# RMII.net
KiCad netlist of a schematic drawn in Altium Designer
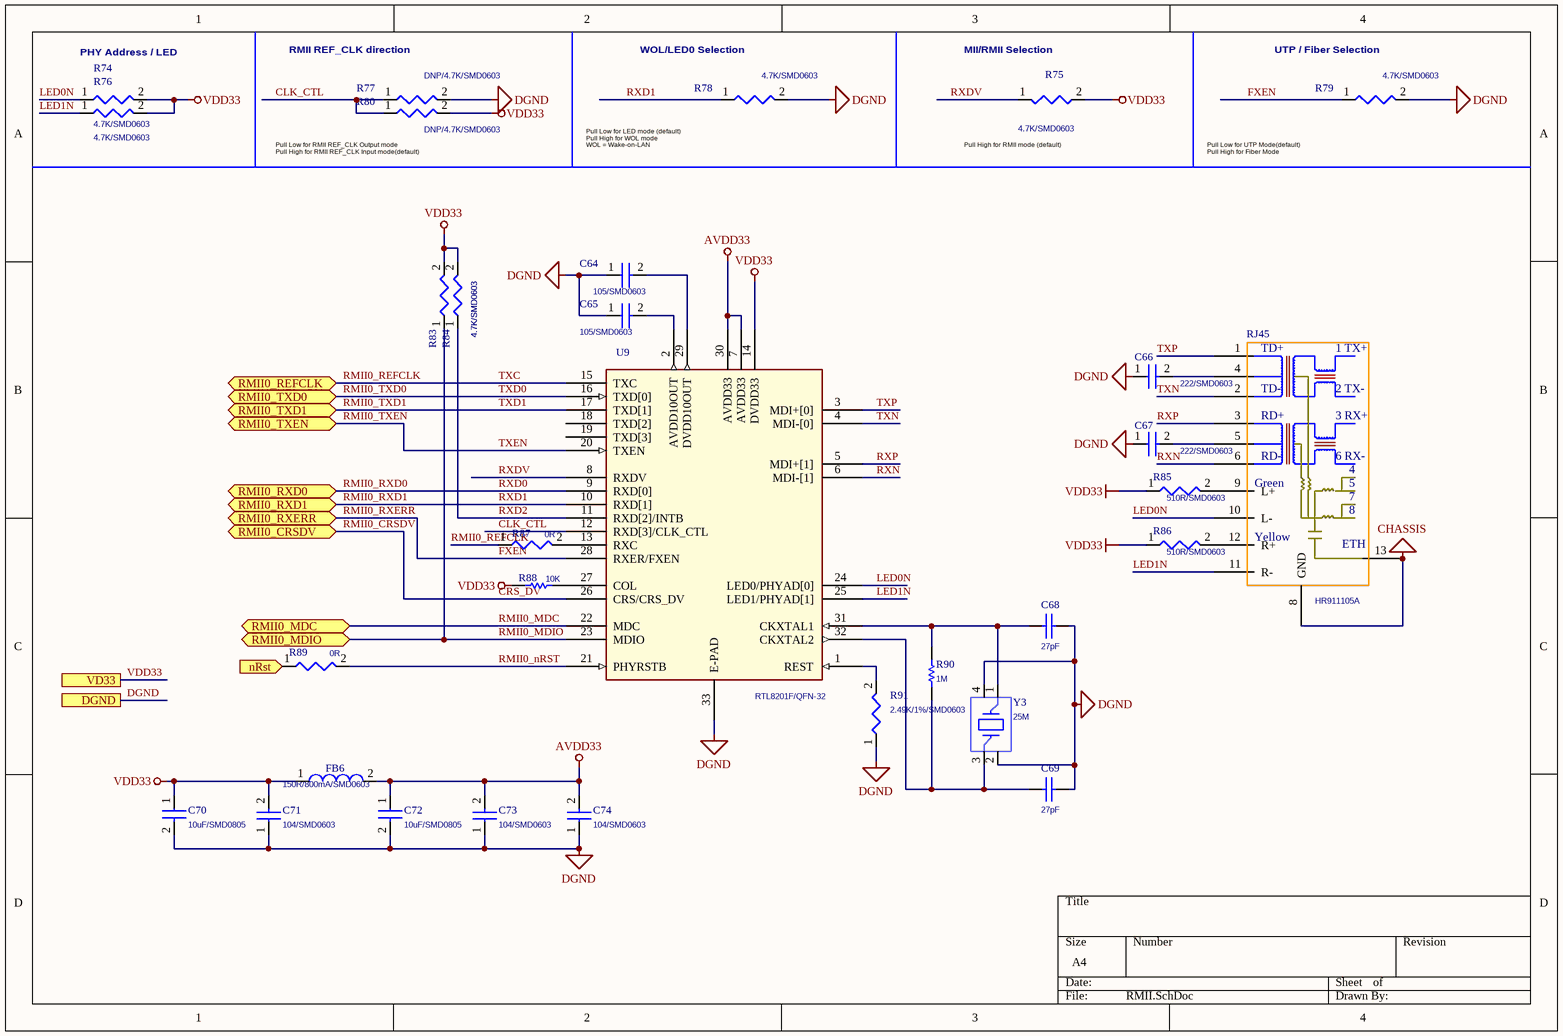
[diagram p0: RMII.SchDoc]

(export (version "E")
  (design (tool "Eeschema 10.0.6"))
  (components
    (comp (ref "C64") (value "105/SMD0603") (footprint "0603C") (libsource (lib "*") (part "C/SMD0603")))
    (comp (ref "C65") (value "105/SMD0603") (footprint "0603C") (libsource (lib "*") (part "C/SMD0603")))
    (comp (ref "C66") (value "222/SMD0603") (footprint "0603C") (libsource (lib "*") (part "C/SMD0603")))
    (comp (ref "C67") (value "222/SMD0603") (footprint "0603C") (libsource (lib "*") (part "C/SMD0603")))
    (comp (ref "C68")
      (value "27pF")
      (footprint "0603C")
      (description "Capacitor")
      (libsource (lib "STM32F103ZET6") (part "CAP"))
    )
    (comp (ref "C69")
      (value "27pF")
      (footprint "0603C")
      (description "Capacitor")
      (libsource (lib "STM32F103ZET6") (part "CAP"))
    )
    (comp (ref "C70") (value "10uF/SMD0805") (footprint "C0805") (libsource (lib "*") (part "C/SMD0805")))
    (comp (ref "C71") (value "104/SMD0603") (footprint "0603C") (libsource (lib "*") (part "C/SMD0603")))
    (comp (ref "C72") (value "10uF/SMD0805") (footprint "C0805") (libsource (lib "*") (part "C/SMD0805")))
    (comp (ref "C73") (value "104/SMD0603") (footprint "0603C") (libsource (lib "*") (part "C/SMD0603")))
    (comp (ref "C74") (value "104/SMD0603") (footprint "0603C") (libsource (lib "*") (part "C/SMD0603")))
    (comp (ref "FB6")
      (value "150R/800mA/SMD0603")
      (footprint "0603R")
      (libsource (lib "*") (part "FB/SMD0603"))
    )
    (comp (ref "R74") (value "4.7K/SMD0603") (footprint "0603R") (libsource (lib "*") (part "R/SMD0603")))
    (comp (ref "R75") (value "4.7K/SMD0603") (footprint "0603R") (libsource (lib "*") (part "R/SMD0603")))
    (comp (ref "R76") (value "4.7K/SMD0603") (footprint "0603R") (libsource (lib "*") (part "R/SMD0603")))
    (comp (ref "R77") (value "DNP/4.7K/SMD0603") (footprint "0603R") (libsource (lib "*") (part "R/SMD0603")))
    (comp (ref "R78") (value "4.7K/SMD0603") (footprint "0603R") (libsource (lib "*") (part "R/SMD0603")))
    (comp (ref "R79") (value "4.7K/SMD0603") (footprint "0603R") (libsource (lib "*") (part "R/SMD0603")))
    (comp (ref "R80") (value "DNP/4.7K/SMD0603") (footprint "0603R") (libsource (lib "*") (part "R/SMD0603")))
    (comp (ref "R83") (value "4.7K/SMD0603") (footprint "0603R") (libsource (lib "*") (part "R/SMD0603")))
    (comp (ref "R84") (value "4.7K/SMD0603") (footprint "0603R") (libsource (lib "*") (part "R/SMD0603")))
    (comp (ref "R85") (value "510R/SMD0603") (footprint "0603R") (libsource (lib "*") (part "R/SMD0603")))
    (comp (ref "R86") (value "510R/SMD0603") (footprint "0603R") (libsource (lib "*") (part "R/SMD0603")))
    (comp (ref "R87") (value "0R") (footprint "0603R") (libsource (lib "*") (part "R/SMD0603")))
    (comp (ref "R88")
      (value "10K")
      (footprint "0603C")
      (description "Resistor")
      (fields (field (name "PUBLISHER") "Altium Limited"))
      (libsource (lib "STM32F103ZET6") (part "Res1"))
    )
    (comp (ref "R89") (value "0R") (footprint "0603R") (libsource (lib "*") (part "R/SMD0603")))
    (comp (ref "R90")
      (value "1M")
      (footprint "0603C")
      (description "Resistor")
      (fields (field (name "PUBLISHER") "Altium Limited"))
      (libsource (lib "STM32F103ZET6") (part "Res1"))
    )
    (comp (ref "R91") (value "2.49K/1%/SMD0603") (footprint "0603R") (libsource (lib "*") (part "R/SMD0603")))
    (comp (ref "RJ45")
      (value "HR911105A")
      (footprint "HR911105A")
      (libsource (lib "changyong") (part "HR911105A"))
    )
    (comp (ref "U9")
      (value "RTL8201F/QFN-32")
      (footprint "QFN32")
      (libsource (lib "*") (part "RTL8201F/QFN-32"))
    )
    (comp (ref "Y3") (value "25M") (footprint "HCX-3SB3225") (libsource (lib "changyong") (part "12Mhz")))
  )
  (nets
    (net (code "1") (name "/CLK_CTL") (class "Default")
      (node (ref "R77") (pin "1") (pinfunction "1_1") (pintype "passive"))
      (node (ref "R80") (pin "1") (pinfunction "1_1") (pintype "passive"))
      (node (ref "U9") (pin "12") (pinfunction "RXD[3]/CLK_CTL_12") (pintype "passive"))
    )
    (net (code "2") (name "/CRS_DV") (class "Default")
      (node (ref "U9") (pin "26") (pinfunction "CRS/CRS_DV_26") (pintype "passive"))
    )
    (net (code "3") (name "/FXEN") (class "Default")
      (node (ref "R79") (pin "1") (pinfunction "1_1") (pintype "passive"))
      (node (ref "U9") (pin "28") (pinfunction "RXER/FXEN_28") (pintype "passive"))
    )
    (net (code "4") (name "/LED0N") (class "Default")
      (node (ref "R74") (pin "1") (pinfunction "1_1") (pintype "passive"))
      (node (ref "RJ45") (pin "10") (pinfunction "L-_10") (pintype "passive"))
      (node (ref "U9") (pin "24") (pinfunction "LED0/PHYAD[0]_24") (pintype "passive"))
    )
    (net (code "5") (name "/LED1N") (class "Default")
      (node (ref "R76") (pin "1") (pinfunction "1_1") (pintype "passive"))
      (node (ref "RJ45") (pin "11") (pinfunction "R-_11") (pintype "passive"))
      (node (ref "U9") (pin "25") (pinfunction "LED1/PHYAD[1]_25") (pintype "passive"))
    )
    (net (code "6") (name "/RMII0_MDC") (class "Default")
      (node (ref "U9") (pin "22") (pinfunction "MDC_22") (pintype "passive"))
    )
    (net (code "7") (name "/RMII0_MDIO") (class "Default")
      (node (ref "R83") (pin "1") (pinfunction "1_1") (pintype "passive"))
      (node (ref "U9") (pin "23") (pinfunction "MDIO_23") (pintype "passive"))
    )
    (net (code "8") (name "/RMII0_REFCLK") (class "Default")
      (node (ref "R87") (pin "1") (pinfunction "1_1") (pintype "passive"))
      (node (ref "U9") (pin "15") (pinfunction "TXC_15") (pintype "passive"))
    )
    (net (code "9") (name "/RMII0_RXD0") (class "Default")
      (node (ref "U9") (pin "9") (pinfunction "RXD[0]_9") (pintype "passive"))
    )
    (net (code "10") (name "/RMII0_RXD1") (class "Default")
      (node (ref "R78") (pin "1") (pinfunction "1_1") (pintype "passive"))
      (node (ref "U9") (pin "10") (pinfunction "RXD[1]_10") (pintype "passive"))
    )
    (net (code "11") (name "/RMII0_TXD0") (class "Default")
      (node (ref "U9") (pin "16") (pinfunction "TXD[0]_16") (pintype "input"))
    )
    (net (code "12") (name "/RMII0_TXD1") (class "Default")
      (node (ref "U9") (pin "17") (pinfunction "TXD[1]_17") (pintype "passive"))
    )
    (net (code "13") (name "/RMII0_TXEN") (class "Default")
      (node (ref "U9") (pin "20") (pinfunction "TXEN_20") (pintype "input"))
    )
    (net (code "14") (name "/RMII0_nRST") (class "Default")
      (node (ref "R89") (pin "2") (pinfunction "2_2") (pintype "passive"))
      (node (ref "U9") (pin "21") (pinfunction "PHYRSTB_21") (pintype "input"))
    )
    (net (code "15") (name "/RXD2") (class "Default")
      (node (ref "R84") (pin "1") (pinfunction "1_1") (pintype "passive"))
      (node (ref "U9") (pin "11") (pinfunction "RXD[2]/INTB_11") (pintype "passive"))
    )
    (net (code "16") (name "/RXDV") (class "Default")
      (node (ref "R75") (pin "1") (pinfunction "1_1") (pintype "passive"))
      (node (ref "U9") (pin "8") (pinfunction "RXDV_8") (pintype "passive"))
    )
    (net (code "17") (name "/RXN") (class "Default")
      (node (ref "RJ45") (pin "6") (pintype "passive"))
      (node (ref "U9") (pin "6") (pinfunction "MDI-[1]_6") (pintype "passive"))
    )
    (net (code "18") (name "/RXP") (class "Default")
      (node (ref "RJ45") (pin "3") (pintype "passive"))
      (node (ref "U9") (pin "5") (pinfunction "MDI+[1]_5") (pintype "passive"))
    )
    (net (code "19") (name "/TXN") (class "Default")
      (node (ref "RJ45") (pin "2") (pintype "passive"))
      (node (ref "U9") (pin "4") (pinfunction "MDI-[0]_4") (pintype "passive"))
    )
    (net (code "20") (name "/TXP") (class "Default")
      (node (ref "RJ45") (pin "1") (pintype "passive"))
      (node (ref "U9") (pin "3") (pinfunction "MDI+[0]_3") (pintype "passive"))
    )
    (net (code "21") (name "/nRst") (class "Default")
      (node (ref "R89") (pin "1") (pinfunction "1_1") (pintype "passive"))
    )
    (net (code "22") (name "AVDD33") (class "Default")
      (node (ref "C72") (pin "1") (pinfunction "1_1") (pintype "passive"))
      (node (ref "C73") (pin "2") (pinfunction "2_2") (pintype "passive"))
      (node (ref "C74") (pin "2") (pinfunction "2_2") (pintype "passive"))
      (node (ref "FB6") (pin "2") (pinfunction "2_2") (pintype "passive"))
      (node (ref "U9") (pin "30") (pinfunction "AVDD33_30") (pintype "power_in"))
      (node (ref "U9") (pin "7") (pinfunction "AVDD33_7") (pintype "power_in"))
    )
    (net (code "23") (name "CHASSIS") (class "Default")
      (node (ref "RJ45") (pin "13") (pintype "passive"))
      (node (ref "RJ45") (pin "8") (pinfunction "GND_8") (pintype "passive"))
    )
    (net (code "24") (name "DGND") (class "Default")
      (node (ref "C64") (pin "1") (pinfunction "1_1") (pintype "passive"))
      (node (ref "C65") (pin "1") (pinfunction "1_1") (pintype "passive"))
      (node (ref "C66") (pin "1") (pinfunction "1_1") (pintype "passive"))
      (node (ref "C67") (pin "1") (pinfunction "1_1") (pintype "passive"))
      (node (ref "C68") (pin "2") (pinfunction "2_2") (pintype "passive"))
      (node (ref "C69") (pin "2") (pinfunction "2_2") (pintype "passive"))
      (node (ref "C70") (pin "2") (pinfunction "2_2") (pintype "passive"))
      (node (ref "C71") (pin "1") (pinfunction "1_1") (pintype "passive"))
      (node (ref "C72") (pin "2") (pinfunction "2_2") (pintype "passive"))
      (node (ref "C73") (pin "1") (pinfunction "1_1") (pintype "passive"))
      (node (ref "C74") (pin "1") (pinfunction "1_1") (pintype "passive"))
      (node (ref "R77") (pin "2") (pinfunction "2_2") (pintype "passive"))
      (node (ref "R78") (pin "2") (pinfunction "2_2") (pintype "passive"))
      (node (ref "R79") (pin "2") (pinfunction "2_2") (pintype "passive"))
      (node (ref "R91") (pin "1") (pinfunction "1_1") (pintype "passive"))
      (node (ref "U9") (pin "33") (pinfunction "E-PAD_33") (pintype "passive"))
      (node (ref "Y3") (pin "2") (pinfunction "2_2") (pintype "passive"))
      (node (ref "Y3") (pin "4") (pinfunction "4_4") (pintype "passive"))
    )
    (net (code "25") (name "Net-(C66-Pad2)") (class "Default")
      (node (ref "C66") (pin "2") (pinfunction "2_2") (pintype "passive"))
      (node (ref "RJ45") (pin "4") (pintype "passive"))
    )
    (net (code "26") (name "Net-(C67-Pad2)") (class "Default")
      (node (ref "C67") (pin "2") (pinfunction "2_2") (pintype "passive"))
      (node (ref "RJ45") (pin "5") (pintype "passive"))
    )
    (net (code "27") (name "Net-(RJ45-L+)") (class "Default")
      (node (ref "R85") (pin "2") (pinfunction "2_2") (pintype "passive"))
      (node (ref "RJ45") (pin "9") (pinfunction "L+_9") (pintype "passive"))
    )
    (net (code "28") (name "Net-(RJ45-R+)") (class "Default")
      (node (ref "R86") (pin "2") (pinfunction "2_2") (pintype "passive"))
      (node (ref "RJ45") (pin "12") (pinfunction "R+_12") (pintype "passive"))
    )
    (net (code "29") (name "Net-(U9-AVDD10OUT)") (class "Default")
      (node (ref "C65") (pin "2") (pinfunction "2_2") (pintype "passive"))
      (node (ref "U9") (pin "2") (pinfunction "AVDD10OUT_2") (pintype "output"))
    )
    (net (code "30") (name "Net-(U9-CKXTAL1)") (class "Default")
      (node (ref "C68") (pin "1") (pinfunction "1_1") (pintype "passive"))
      (node (ref "R90") (pin "2") (pinfunction "2_2") (pintype "passive"))
      (node (ref "U9") (pin "31") (pinfunction "CKXTAL1_31") (pintype "input"))
      (node (ref "Y3") (pin "1") (pinfunction "1_1") (pintype "passive"))
    )
    (net (code "31") (name "Net-(U9-CKXTAL2)") (class "Default")
      (node (ref "C69") (pin "1") (pinfunction "1_1") (pintype "passive"))
      (node (ref "R90") (pin "1") (pinfunction "1_1") (pintype "passive"))
      (node (ref "U9") (pin "32") (pinfunction "CKXTAL2_32") (pintype "output"))
      (node (ref "Y3") (pin "3") (pinfunction "3_3") (pintype "passive"))
    )
    (net (code "32") (name "Net-(U9-COL)") (class "Default")
      (node (ref "R88") (pin "1") (pinfunction "1_1") (pintype "passive"))
      (node (ref "U9") (pin "27") (pinfunction "COL_27") (pintype "passive"))
    )
    (net (code "33") (name "Net-(U9-DVDD10OUT)") (class "Default")
      (node (ref "C64") (pin "2") (pinfunction "2_2") (pintype "passive"))
      (node (ref "U9") (pin "29") (pinfunction "DVDD10OUT_29") (pintype "output"))
    )
    (net (code "34") (name "Net-(U9-REST)") (class "Default")
      (node (ref "R91") (pin "2") (pinfunction "2_2") (pintype "passive"))
      (node (ref "U9") (pin "1") (pinfunction "REST_1") (pintype "input"))
    )
    (net (code "35") (name "Net-(U9-RXC)") (class "Default")
      (node (ref "R87") (pin "2") (pinfunction "2_2") (pintype "passive"))
      (node (ref "U9") (pin "13") (pinfunction "RXC_13") (pintype "passive"))
    )
    (net (code "36") (name "VDD33") (class "Default")
      (node (ref "C70") (pin "1") (pinfunction "1_1") (pintype "passive"))
      (node (ref "C71") (pin "2") (pinfunction "2_2") (pintype "passive"))
      (node (ref "FB6") (pin "1") (pinfunction "1_1") (pintype "passive"))
      (node (ref "R74") (pin "2") (pinfunction "2_2") (pintype "passive"))
      (node (ref "R75") (pin "2") (pinfunction "2_2") (pintype "passive"))
      (node (ref "R76") (pin "2") (pinfunction "2_2") (pintype "passive"))
      (node (ref "R80") (pin "2") (pinfunction "2_2") (pintype "passive"))
      (node (ref "R83") (pin "2") (pinfunction "2_2") (pintype "passive"))
      (node (ref "R84") (pin "2") (pinfunction "2_2") (pintype "passive"))
      (node (ref "R85") (pin "1") (pinfunction "1_1") (pintype "passive"))
      (node (ref "R86") (pin "1") (pinfunction "1_1") (pintype "passive"))
      (node (ref "R88") (pin "2") (pinfunction "2_2") (pintype "passive"))
      (node (ref "U9") (pin "14") (pinfunction "DVDD33_14") (pintype "power_in"))
    )
    (net (code "37") (name "unconnected-(U9-TXD[2]-Pad18)") (class "Default")
      (node (ref "U9") (pin "18") (pinfunction "TXD[2]_18") (pintype "passive"))
    )
    (net (code "38") (name "unconnected-(U9-TXD[3]-Pad19)") (class "Default")
      (node (ref "U9") (pin "19") (pinfunction "TXD[3]_19") (pintype "passive"))
    )
  )
)
